# SwBotMain.net
KiCad netlist of a schematic drawn in EAGLE
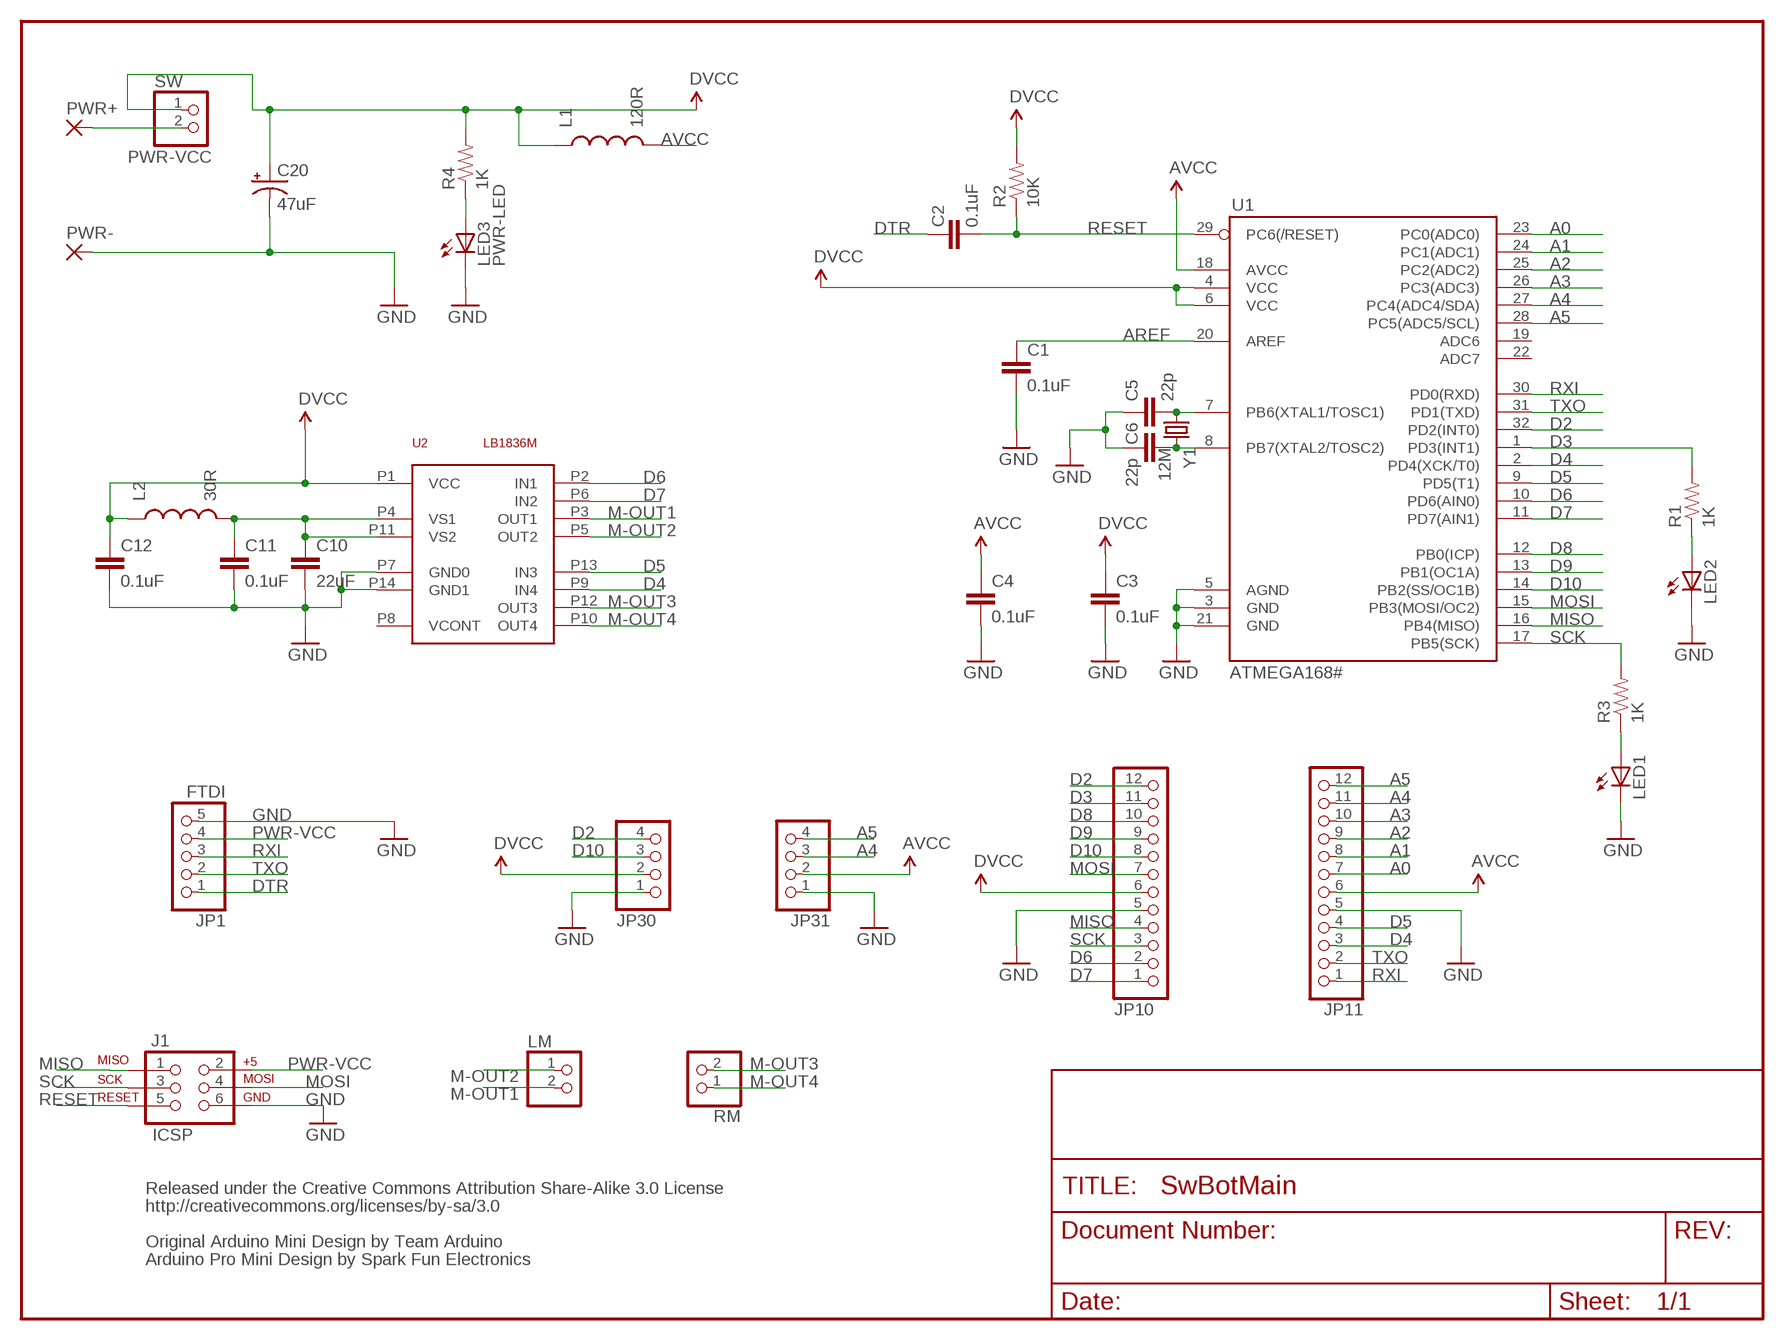
[diagram p0: schematic, sheet 1]

(export (version "E")
  (design (tool "Eeschema 10.0.6"))
  (components
    (comp (ref "C1")
      (value "0.1uF")
      (footprint "eagle-import:0805")
      (libsource (lib "eagle-import") (part "SparkFun-Capacitors_CAP0805"))
    )
    (comp (ref "C2")
      (value "0.1uF")
      (footprint "eagle-import:0805")
      (libsource (lib "eagle-import") (part "CAP0805"))
    )
    (comp (ref "C3")
      (value "0.1uF")
      (footprint "eagle-import:0805")
      (libsource (lib "eagle-import") (part "SparkFun-Capacitors_CAP0805"))
    )
    (comp (ref "C4")
      (value "0.1uF")
      (footprint "eagle-import:0805")
      (libsource (lib "eagle-import") (part "SparkFun-Capacitors_CAP0805"))
    )
    (comp (ref "C5")
      (value "22p")
      (footprint "eagle-import:0805")
      (libsource (lib "eagle-import") (part "SparkFun-Capacitors_CAP0805"))
    )
    (comp (ref "C6")
      (value "22p")
      (footprint "eagle-import:0805")
      (libsource (lib "eagle-import") (part "SparkFun-Capacitors_CAP0805"))
    )
    (comp (ref "C10")
      (value "22uF")
      (footprint "eagle-import:1206")
      (libsource (lib "eagle-import") (part "CAP1206"))
    )
    (comp (ref "C11")
      (value "0.1uF")
      (footprint "eagle-import:0805")
      (libsource (lib "eagle-import") (part "SparkFun-Capacitors_CAP0805"))
    )
    (comp (ref "C12")
      (value "0.1uF")
      (footprint "eagle-import:0805")
      (libsource (lib "eagle-import") (part "SparkFun-Capacitors_CAP0805"))
    )
    (comp (ref "C20")
      (value "47uF")
      (footprint "eagle-import:EIA3528")
      (libsource (lib "eagle-import") (part "47UF-TANT"))
    )
    (comp (ref "J1")
      (value "ICSP")
      (footprint "eagle-import:2X3_LOCK")
      (libsource (lib "eagle-import") (part "AVR_SPI_PRG_62X3_LOCK"))
    )
    (comp (ref "JP1")
      (value "FTDI")
      (footprint "eagle-import:1X05")
      (libsource (lib "eagle-import") (part "PINHD-1X5"))
    )
    (comp (ref "JP10")
      (value "PINHD-1X12")
      (footprint "eagle-import:1X12")
      (libsource (lib "eagle-import") (part "PINHD-1X12"))
    )
    (comp (ref "JP11")
      (value "PINHD-1X12")
      (footprint "eagle-import:1X12")
      (libsource (lib "eagle-import") (part "PINHD-1X12"))
    )
    (comp (ref "JP30")
      (value "PINHD-1X4")
      (footprint "eagle-import:1X04")
      (libsource (lib "eagle-import") (part "PINHD-1X4"))
    )
    (comp (ref "JP31")
      (value "PINHD-1X4")
      (footprint "eagle-import:1X04")
      (libsource (lib "eagle-import") (part "PINHD-1X4"))
    )
    (comp (ref "L1")
      (value "120R")
      (footprint "eagle-import:0805")
      (libsource (lib "eagle-import") (part "INDUCTOR0805"))
    )
    (comp (ref "L2")
      (value "30R")
      (footprint "eagle-import:0805")
      (libsource (lib "eagle-import") (part "INDUCTOR0805"))
    )
    (comp (ref "LED1")
      (value "LEDCHIP-LED0805")
      (footprint "eagle-import:CHIP-LED0805")
      (libsource (lib "eagle-import") (part "LEDCHIP-LED0805"))
    )
    (comp (ref "LED2")
      (value "LEDCHIP-LED0805")
      (footprint "eagle-import:CHIP-LED0805")
      (libsource (lib "eagle-import") (part "LEDCHIP-LED0805"))
    )
    (comp (ref "LED3")
      (value "PWR-LED")
      (footprint "eagle-import:LED5MM")
      (libsource (lib "eagle-import") (part "LED5MM"))
    )
    (comp (ref "LM")
      (value "PINHD-1X2")
      (footprint "eagle-import:1X02")
      (libsource (lib "eagle-import") (part "PINHD-1X2"))
    )
    (comp (ref "PWR+")
      (value "SMD2")
      (footprint "eagle-import:SMD1,27-2,54")
      (libsource (lib "eagle-import") (part "SMD2"))
    )
    (comp (ref "PWR-")
      (value "SMD2")
      (footprint "eagle-import:SMD1,27-2,54")
      (libsource (lib "eagle-import") (part "SMD2"))
    )
    (comp (ref "R1")
      (value "1K")
      (footprint "eagle-import:0805")
      (libsource (lib "eagle-import") (part "RESISTOR0805-RES"))
    )
    (comp (ref "R2")
      (value "10K")
      (footprint "eagle-import:0805")
      (libsource (lib "eagle-import") (part "RESISTOR0805-RES"))
    )
    (comp (ref "R3")
      (value "1K")
      (footprint "eagle-import:0805")
      (libsource (lib "eagle-import") (part "RESISTOR0805-RES"))
    )
    (comp (ref "R4")
      (value "1K")
      (footprint "eagle-import:0805")
      (libsource (lib "eagle-import") (part "RESISTOR0805-RES"))
    )
    (comp (ref "RM")
      (value "PINHD-1X2")
      (footprint "eagle-import:1X02")
      (libsource (lib "eagle-import") (part "PINHD-1X2"))
    )
    (comp (ref "SW")
      (value "PINHD-1X2")
      (footprint "eagle-import:1X02")
      (libsource (lib "eagle-import") (part "PINHD-1X2"))
    )
    (comp (ref "U1")
      (value "ATMEGA168#")
      (footprint "eagle-import:TQFP32-08")
      (libsource (lib "eagle-import") (part "ATMEGA168"))
    )
    (comp (ref "U2")
      (value "LB1836M")
      (footprint "eagle-import:MFP14S")
      (libsource (lib "eagle-import") (part "LB1836M"))
    )
    (comp (ref "Y1")
      (value "12M")
      (footprint "eagle-import:CRYSTAL-TXC-7A")
      (libsource (lib "eagle-import") (part "CRYSTALTXC-7A"))
    )
  )
  (nets
    (net (code "1") (name "/A0") (class "Default")
      (node (ref "JP11") (pin "7") (pinfunction "7_7") (pintype "passive"))
      (node (ref "U1") (pin "23") (pinfunction "PC0(ADC0)_23") (pintype "bidirectional"))
    )
    (net (code "2") (name "/A1") (class "Default")
      (node (ref "JP11") (pin "8") (pinfunction "8_8") (pintype "passive"))
      (node (ref "U1") (pin "24") (pinfunction "PC1(ADC1)_24") (pintype "bidirectional"))
    )
    (net (code "3") (name "/A2") (class "Default")
      (node (ref "JP11") (pin "9") (pinfunction "9_9") (pintype "passive"))
      (node (ref "U1") (pin "25") (pinfunction "PC2(ADC2)_25") (pintype "bidirectional"))
    )
    (net (code "4") (name "/A3") (class "Default")
      (node (ref "JP11") (pin "10") (pinfunction "10_10") (pintype "passive"))
      (node (ref "U1") (pin "26") (pinfunction "PC3(ADC3)_26") (pintype "bidirectional"))
    )
    (net (code "5") (name "/A4") (class "Default")
      (node (ref "JP11") (pin "11") (pinfunction "11_11") (pintype "passive"))
      (node (ref "JP31") (pin "3") (pinfunction "3_3") (pintype "passive"))
      (node (ref "U1") (pin "27") (pinfunction "PC4(ADC4/SDA)_27") (pintype "bidirectional"))
    )
    (net (code "6") (name "/A5") (class "Default")
      (node (ref "JP11") (pin "12") (pinfunction "12_12") (pintype "passive"))
      (node (ref "JP31") (pin "4") (pinfunction "4_4") (pintype "passive"))
      (node (ref "U1") (pin "28") (pinfunction "PC5(ADC5/SCL)_28") (pintype "bidirectional"))
    )
    (net (code "7") (name "/AREF") (class "Default")
      (node (ref "C1") (pin "1") (pinfunction "1_1") (pintype "passive"))
      (node (ref "U1") (pin "20") (pinfunction "AREF_20") (pintype "bidirectional"))
    )
    (net (code "8") (name "/D2") (class "Default")
      (node (ref "JP10") (pin "12") (pinfunction "12_12") (pintype "passive"))
      (node (ref "JP30") (pin "4") (pinfunction "4_4") (pintype "passive"))
      (node (ref "U1") (pin "32") (pinfunction "PD2(INT0)_32") (pintype "bidirectional"))
    )
    (net (code "9") (name "/D3") (class "Default")
      (node (ref "JP10") (pin "11") (pinfunction "11_11") (pintype "passive"))
      (node (ref "R1") (pin "2") (pinfunction "2_2") (pintype "passive"))
      (node (ref "U1") (pin "1") (pinfunction "PD3(INT1)_1") (pintype "bidirectional"))
    )
    (net (code "10") (name "/D4") (class "Default")
      (node (ref "JP11") (pin "3") (pinfunction "3_3") (pintype "passive"))
      (node (ref "U1") (pin "2") (pinfunction "PD4(XCK/T0)_2") (pintype "bidirectional"))
      (node (ref "U2") (pin "P9") (pinfunction "IN4_P9") (pintype "input"))
    )
    (net (code "11") (name "/D5") (class "Default")
      (node (ref "JP11") (pin "4") (pinfunction "4_4") (pintype "passive"))
      (node (ref "U1") (pin "9") (pinfunction "PD5(T1)_9") (pintype "bidirectional"))
      (node (ref "U2") (pin "P13") (pinfunction "IN3_P13") (pintype "input"))
    )
    (net (code "12") (name "/D6") (class "Default")
      (node (ref "JP10") (pin "2") (pinfunction "2_2") (pintype "passive"))
      (node (ref "U1") (pin "10") (pinfunction "PD6(AIN0)_10") (pintype "bidirectional"))
      (node (ref "U2") (pin "P2") (pinfunction "IN1_P2") (pintype "input"))
    )
    (net (code "13") (name "/D7") (class "Default")
      (node (ref "JP10") (pin "1") (pinfunction "1_1") (pintype "passive"))
      (node (ref "U1") (pin "11") (pinfunction "PD7(AIN1)_11") (pintype "bidirectional"))
      (node (ref "U2") (pin "P6") (pinfunction "IN2_P6") (pintype "input"))
    )
    (net (code "14") (name "/D8") (class "Default")
      (node (ref "JP10") (pin "10") (pinfunction "10_10") (pintype "passive"))
      (node (ref "U1") (pin "12") (pinfunction "PB0(ICP)_12") (pintype "bidirectional"))
    )
    (net (code "15") (name "/D9") (class "Default")
      (node (ref "JP10") (pin "9") (pinfunction "9_9") (pintype "passive"))
      (node (ref "U1") (pin "13") (pinfunction "PB1(OC1A)_13") (pintype "bidirectional"))
    )
    (net (code "16") (name "/D10") (class "Default")
      (node (ref "JP10") (pin "8") (pinfunction "8_8") (pintype "passive"))
      (node (ref "JP30") (pin "3") (pinfunction "3_3") (pintype "passive"))
      (node (ref "U1") (pin "14") (pinfunction "PB2(SS/OC1B)_14") (pintype "bidirectional"))
    )
    (net (code "17") (name "/DTR") (class "Default")
      (node (ref "C2") (pin "2") (pinfunction "2_2") (pintype "passive"))
      (node (ref "JP1") (pin "1") (pinfunction "1_1") (pintype "passive"))
    )
    (net (code "18") (name "/M-OUT1") (class "Default")
      (node (ref "LM") (pin "2") (pinfunction "2_2") (pintype "passive"))
      (node (ref "U2") (pin "P3") (pinfunction "OUT1_P3") (pintype "output"))
    )
    (net (code "19") (name "/M-OUT2") (class "Default")
      (node (ref "LM") (pin "1") (pinfunction "1_1") (pintype "passive"))
      (node (ref "U2") (pin "P5") (pinfunction "OUT2_P5") (pintype "output"))
    )
    (net (code "20") (name "/M-OUT3") (class "Default")
      (node (ref "RM") (pin "2") (pinfunction "2_2") (pintype "passive"))
      (node (ref "U2") (pin "P12") (pinfunction "OUT3_P12") (pintype "output"))
    )
    (net (code "21") (name "/M-OUT4") (class "Default")
      (node (ref "RM") (pin "1") (pinfunction "1_1") (pintype "passive"))
      (node (ref "U2") (pin "P10") (pinfunction "OUT4_P10") (pintype "output"))
    )
    (net (code "22") (name "/MISO") (class "Default")
      (node (ref "J1") (pin "1") (pinfunction "1_1") (pintype "passive"))
      (node (ref "JP10") (pin "4") (pinfunction "4_4") (pintype "passive"))
      (node (ref "U1") (pin "16") (pinfunction "PB4(MISO)_16") (pintype "bidirectional"))
    )
    (net (code "23") (name "/MOSI") (class "Default")
      (node (ref "J1") (pin "4") (pinfunction "4_4") (pintype "passive"))
      (node (ref "JP10") (pin "7") (pinfunction "7_7") (pintype "passive"))
      (node (ref "U1") (pin "15") (pinfunction "PB3(MOSI/OC2)_15") (pintype "bidirectional"))
    )
    (net (code "24") (name "/PWR-VCC") (class "Default")
      (node (ref "J1") (pin "2") (pinfunction "2_2") (pintype "passive"))
      (node (ref "JP1") (pin "4") (pinfunction "4_4") (pintype "passive"))
      (node (ref "PWR+") (pin "1") (pinfunction "P_1") (pintype "passive"))
      (node (ref "SW") (pin "2") (pinfunction "2_2") (pintype "passive"))
    )
    (net (code "25") (name "/RESET") (class "Default")
      (node (ref "C2") (pin "1") (pinfunction "1_1") (pintype "passive"))
      (node (ref "J1") (pin "5") (pinfunction "5_5") (pintype "passive"))
      (node (ref "R2") (pin "1") (pinfunction "1_1") (pintype "passive"))
      (node (ref "U1") (pin "29") (pinfunction "PC6(/RESET)_29") (pintype "bidirectional"))
    )
    (net (code "26") (name "/RXI") (class "Default")
      (node (ref "JP1") (pin "3") (pinfunction "3_3") (pintype "passive"))
      (node (ref "JP11") (pin "1") (pinfunction "1_1") (pintype "passive"))
      (node (ref "U1") (pin "30") (pinfunction "PD0(RXD)_30") (pintype "bidirectional"))
    )
    (net (code "27") (name "/SCK") (class "Default")
      (node (ref "J1") (pin "3") (pinfunction "3_3") (pintype "passive"))
      (node (ref "JP10") (pin "3") (pinfunction "3_3") (pintype "passive"))
      (node (ref "R3") (pin "2") (pinfunction "2_2") (pintype "passive"))
      (node (ref "U1") (pin "17") (pinfunction "PB5(SCK)_17") (pintype "bidirectional"))
    )
    (net (code "28") (name "/TXO") (class "Default")
      (node (ref "JP1") (pin "2") (pinfunction "2_2") (pintype "passive"))
      (node (ref "JP11") (pin "2") (pinfunction "2_2") (pintype "passive"))
      (node (ref "U1") (pin "31") (pinfunction "PD1(TXD)_31") (pintype "bidirectional"))
    )
    (net (code "29") (name "AVCC") (class "Default")
      (node (ref "C4") (pin "1") (pinfunction "1_1") (pintype "passive"))
      (node (ref "JP11") (pin "6") (pinfunction "6_6") (pintype "passive"))
      (node (ref "JP31") (pin "2") (pinfunction "2_2") (pintype "passive"))
      (node (ref "L1") (pin "2") (pinfunction "2_2") (pintype "passive"))
      (node (ref "U1") (pin "18") (pinfunction "AVCC_18") (pintype "bidirectional"))
    )
    (net (code "30") (name "DVCC") (class "Default")
      (node (ref "C12") (pin "1") (pinfunction "1_1") (pintype "passive"))
      (node (ref "C20") (pin "A") (pinfunction "+_A") (pintype "passive"))
      (node (ref "C3") (pin "1") (pinfunction "1_1") (pintype "passive"))
      (node (ref "JP10") (pin "6") (pinfunction "6_6") (pintype "passive"))
      (node (ref "JP30") (pin "2") (pinfunction "2_2") (pintype "passive"))
      (node (ref "L1") (pin "1") (pinfunction "1_1") (pintype "passive"))
      (node (ref "L2") (pin "1") (pinfunction "1_1") (pintype "passive"))
      (node (ref "R2") (pin "2") (pinfunction "2_2") (pintype "passive"))
      (node (ref "R4") (pin "2") (pinfunction "2_2") (pintype "passive"))
      (node (ref "SW") (pin "1") (pinfunction "1_1") (pintype "passive"))
      (node (ref "U1") (pin "4") (pinfunction "VCC_4") (pintype "bidirectional"))
      (node (ref "U1") (pin "6") (pinfunction "VCC_6") (pintype "bidirectional"))
      (node (ref "U2") (pin "P1") (pinfunction "VCC_P1") (pintype "power_in"))
    )
    (net (code "31") (name "GND") (class "Default")
      (node (ref "C1") (pin "2") (pinfunction "2_2") (pintype "passive"))
      (node (ref "C10") (pin "2") (pinfunction "2_2") (pintype "passive"))
      (node (ref "C11") (pin "2") (pinfunction "2_2") (pintype "passive"))
      (node (ref "C12") (pin "2") (pinfunction "2_2") (pintype "passive"))
      (node (ref "C20") (pin "C") (pinfunction "-_C") (pintype "passive"))
      (node (ref "C3") (pin "2") (pinfunction "2_2") (pintype "passive"))
      (node (ref "C4") (pin "2") (pinfunction "2_2") (pintype "passive"))
      (node (ref "C5") (pin "1") (pinfunction "1_1") (pintype "passive"))
      (node (ref "C6") (pin "2") (pinfunction "2_2") (pintype "passive"))
      (node (ref "J1") (pin "6") (pinfunction "6_6") (pintype "passive"))
      (node (ref "JP1") (pin "5") (pinfunction "5_5") (pintype "passive"))
      (node (ref "JP10") (pin "5") (pinfunction "5_5") (pintype "passive"))
      (node (ref "JP11") (pin "5") (pinfunction "5_5") (pintype "passive"))
      (node (ref "JP30") (pin "1") (pinfunction "1_1") (pintype "passive"))
      (node (ref "JP31") (pin "1") (pinfunction "1_1") (pintype "passive"))
      (node (ref "LED1") (pin "C") (pinfunction "C_C") (pintype "passive"))
      (node (ref "LED2") (pin "C") (pinfunction "C_C") (pintype "passive"))
      (node (ref "LED3") (pin "K") (pinfunction "C_K") (pintype "passive"))
      (node (ref "PWR-") (pin "1") (pinfunction "P_1") (pintype "passive"))
      (node (ref "U1") (pin "21") (pinfunction "GND_21") (pintype "bidirectional"))
      (node (ref "U1") (pin "3") (pinfunction "GND_3") (pintype "bidirectional"))
      (node (ref "U1") (pin "5") (pinfunction "AGND_5") (pintype "bidirectional"))
      (node (ref "U2") (pin "P14") (pinfunction "GND1_P14") (pintype "power_in"))
      (node (ref "U2") (pin "P7") (pinfunction "GND0_P7") (pintype "power_in"))
    )
    (net (code "32") (name "Net-(LED1-PadA)") (class "Default")
      (node (ref "LED1") (pin "A") (pinfunction "A_A") (pintype "passive"))
      (node (ref "R3") (pin "1") (pinfunction "1_1") (pintype "passive"))
    )
    (net (code "33") (name "Net-(LED2-PadA)") (class "Default")
      (node (ref "LED2") (pin "A") (pinfunction "A_A") (pintype "passive"))
      (node (ref "R1") (pin "1") (pinfunction "1_1") (pintype "passive"))
    )
    (net (code "34") (name "Net-(LED3-PadA)") (class "Default")
      (node (ref "LED3") (pin "A") (pinfunction "A_A") (pintype "passive"))
      (node (ref "R4") (pin "1") (pinfunction "1_1") (pintype "passive"))
    )
    (net (code "35") (name "Net-(U1-PB6(XTAL1{slash}TOSC1))") (class "Default")
      (node (ref "C5") (pin "2") (pinfunction "2_2") (pintype "passive"))
      (node (ref "U1") (pin "7") (pinfunction "PB6(XTAL1/TOSC1)_7") (pintype "bidirectional"))
      (node (ref "Y1") (pin "P$1") (pinfunction "1_P$1") (pintype "passive"))
    )
    (net (code "36") (name "Net-(U1-PB7(XTAL2{slash}TOSC2))") (class "Default")
      (node (ref "C6") (pin "1") (pinfunction "1_1") (pintype "passive"))
      (node (ref "U1") (pin "8") (pinfunction "PB7(XTAL2/TOSC2)_8") (pintype "bidirectional"))
      (node (ref "Y1") (pin "P$2") (pinfunction "2_P$2") (pintype "passive"))
    )
    (net (code "37") (name "Net-(U2-VS1)") (class "Default")
      (node (ref "C10") (pin "1") (pinfunction "1_1") (pintype "passive"))
      (node (ref "C11") (pin "1") (pinfunction "1_1") (pintype "passive"))
      (node (ref "L2") (pin "2") (pinfunction "2_2") (pintype "passive"))
      (node (ref "U2") (pin "P11") (pinfunction "VS2_P11") (pintype "power_in"))
      (node (ref "U2") (pin "P4") (pinfunction "VS1_P4") (pintype "power_in"))
    )
    (net (code "38") (name "unconnected-(U1-ADC6-Pad19)") (class "Default")
      (node (ref "U1") (pin "19") (pinfunction "ADC6_19") (pintype "bidirectional"))
    )
    (net (code "39") (name "unconnected-(U1-ADC7-Pad22)") (class "Default")
      (node (ref "U1") (pin "22") (pinfunction "ADC7_22") (pintype "bidirectional"))
    )
    (net (code "40") (name "unconnected-(U2-VCONT-PadP8)") (class "Default")
      (node (ref "U2") (pin "P8") (pinfunction "VCONT_P8") (pintype "output"))
    )
  )
)
